# VM3300_V0_1.net
KiCad netlist of a schematic drawn in Altium Designer
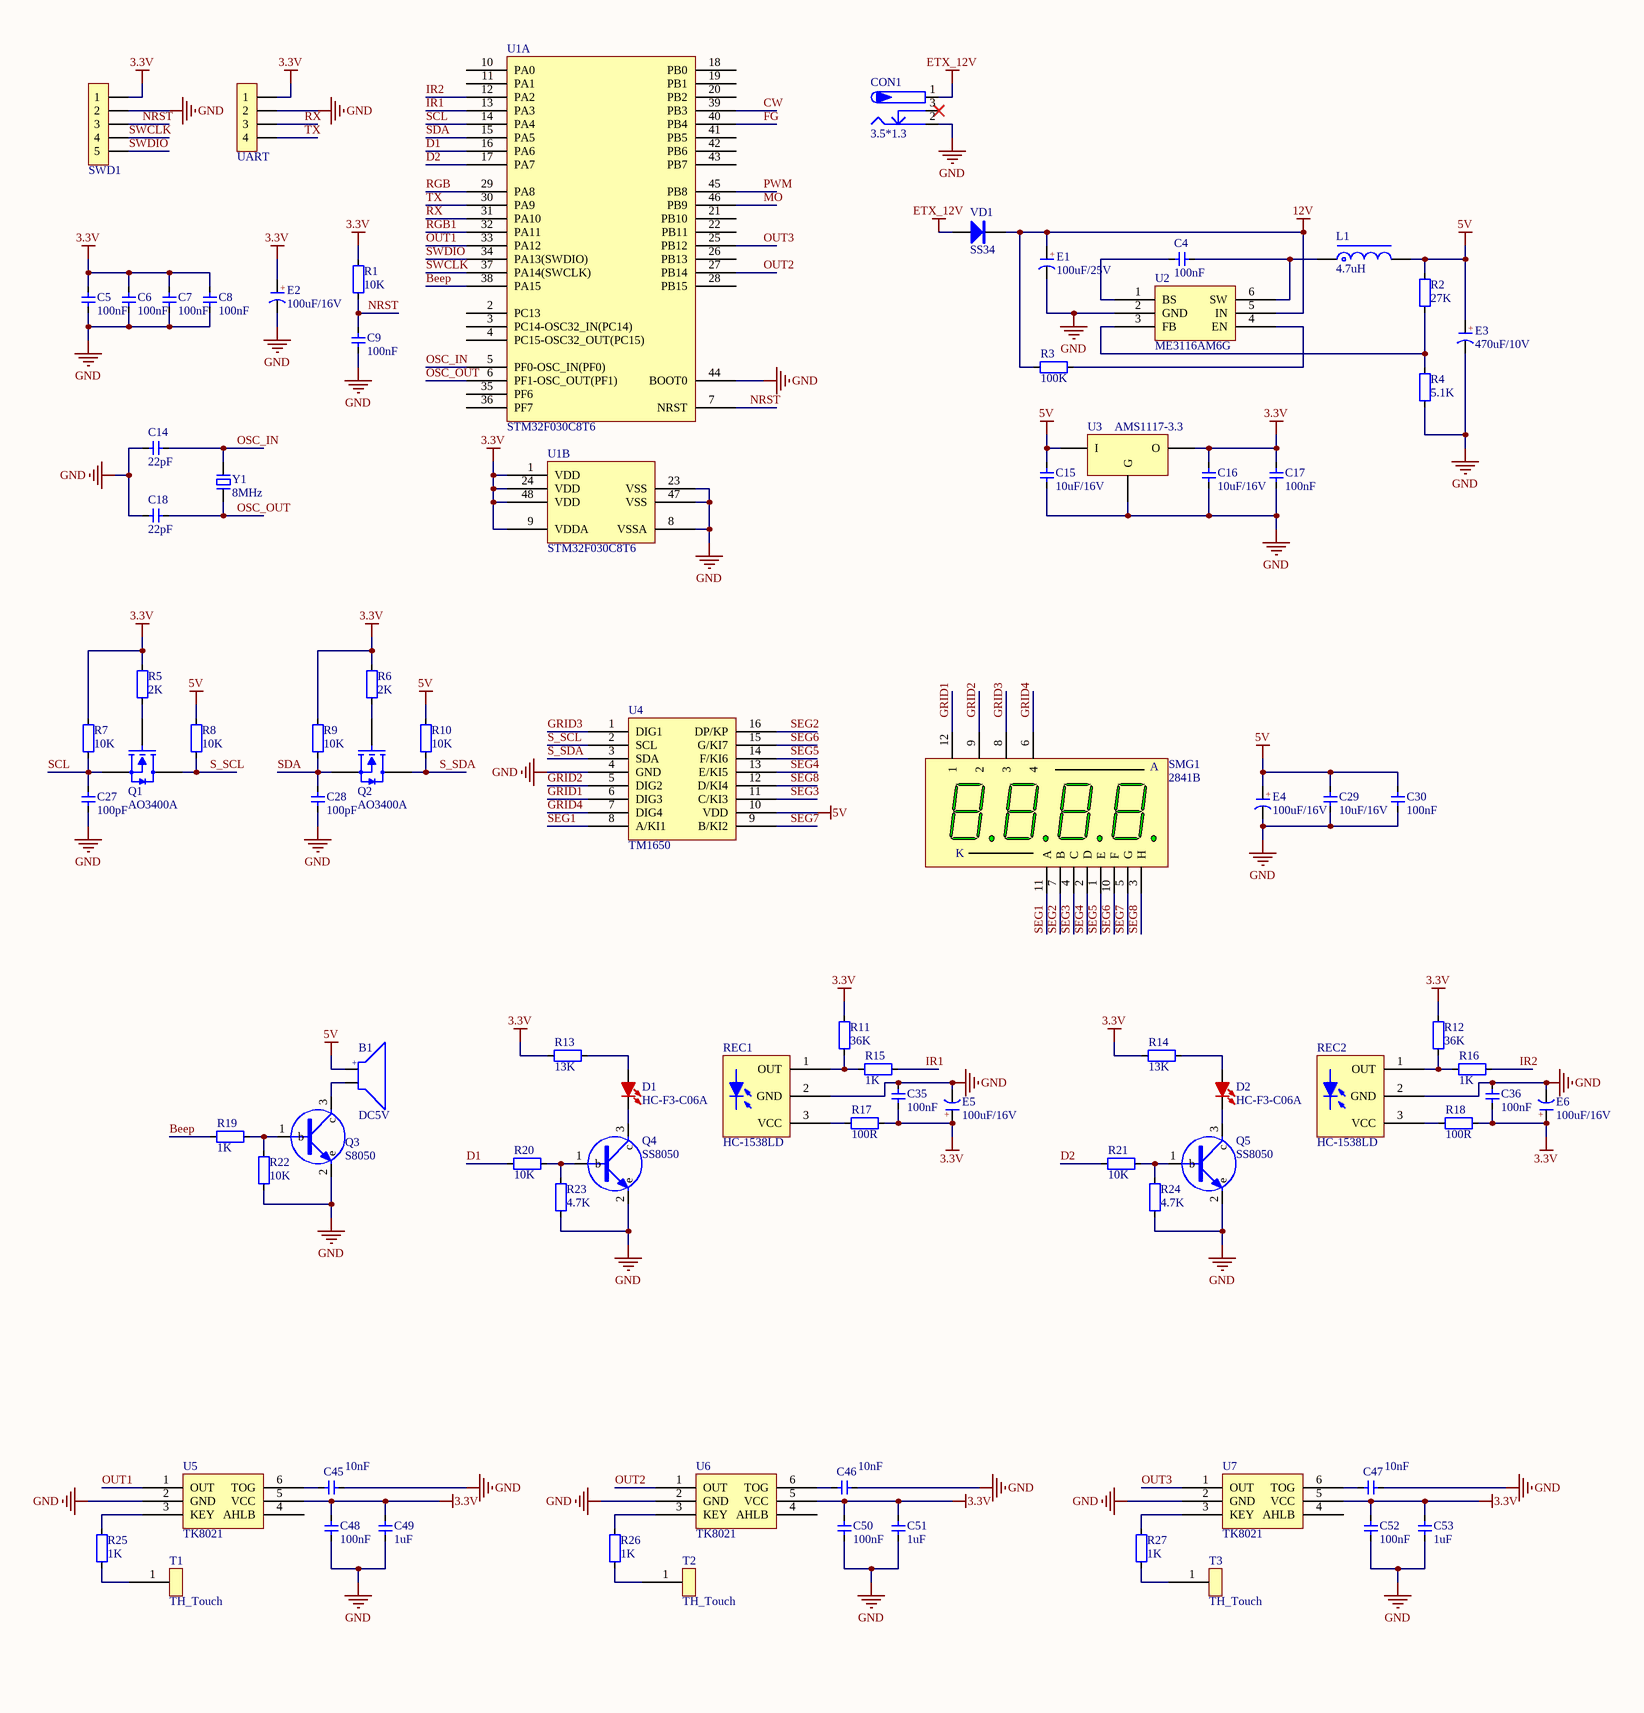
[diagram p0: VM3300_V0.1.SchDoc, left]
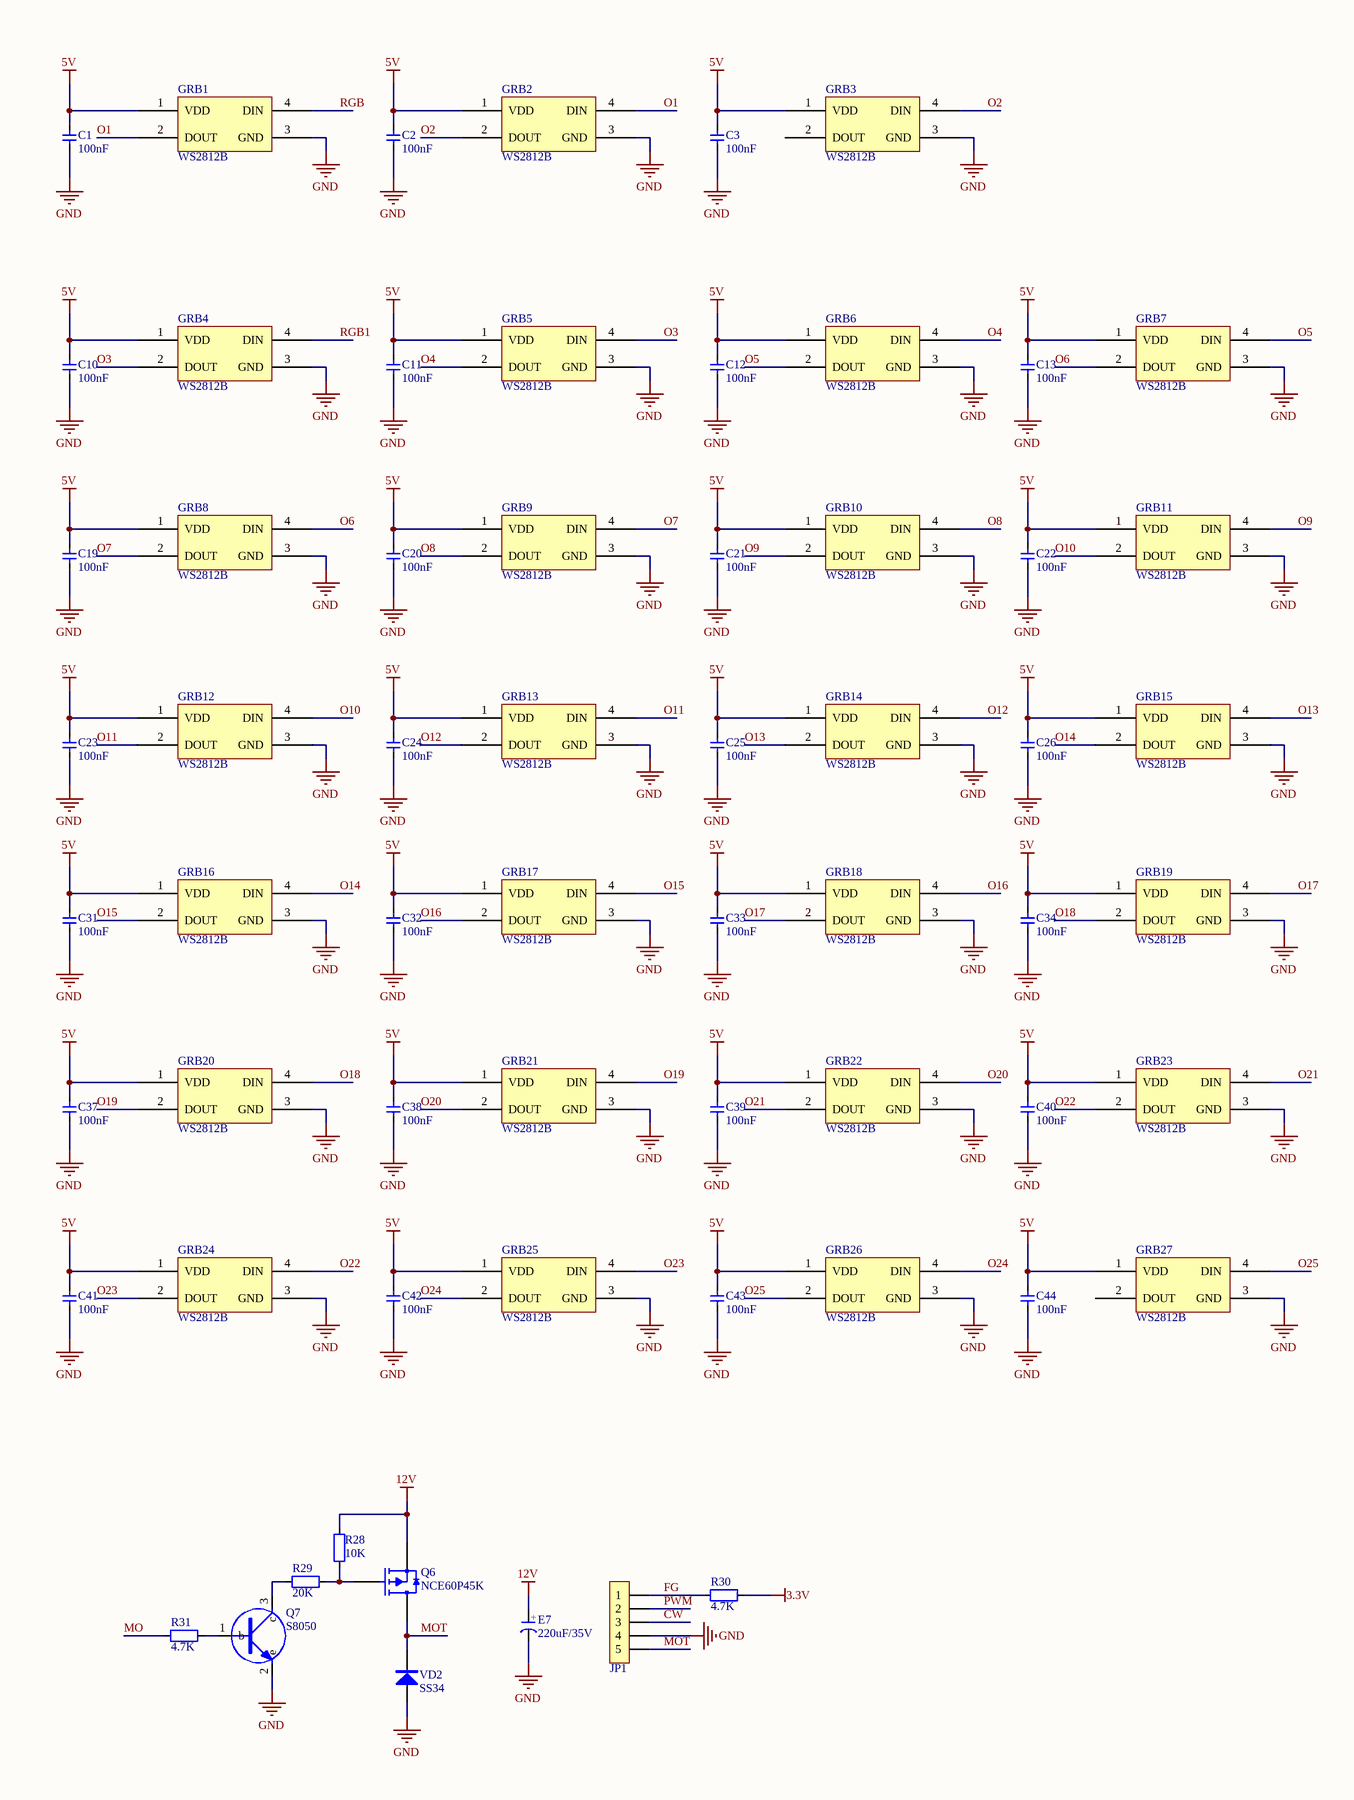
[diagram p1: VM3300_V0.1.SchDoc, right]

(export (version "E")
  (design (tool "Eeschema 10.0.6"))
  (components
    (comp (ref "B1")
      (value "DC5V")
      (footprint "BEEP 7.6x12x7.5")
      (description "蜂鸣器")
      (fields (field (name "版权归属") "源创客"))
      (libsource (lib "模块器件") (part "BEEP"))
    )
    (comp (ref "C1")
      (value "100nF")
      (footprint "C 0603")
      (description "无极性贴片电容")
      (fields (field (name "版权归属") "源创客"))
      (libsource (lib "电容") (part "C"))
    )
    (comp (ref "C2")
      (value "100nF")
      (footprint "C 0603")
      (description "无极性贴片电容")
      (fields (field (name "版权归属") "源创客"))
      (libsource (lib "电容") (part "C"))
    )
    (comp (ref "C3")
      (value "100nF")
      (footprint "C 0603")
      (description "无极性贴片电容")
      (fields (field (name "版权归属") "源创客"))
      (libsource (lib "电容") (part "C"))
    )
    (comp (ref "C4")
      (value "100nF")
      (footprint "C 0603")
      (description "无极性贴片电容")
      (fields (field (name "版权归属") "源创客"))
      (libsource (lib "电容") (part "C"))
    )
    (comp (ref "C5")
      (value "100nF")
      (footprint "C 0603")
      (description "无极性贴片电容")
      (fields (field (name "版权归属") "源创客"))
      (libsource (lib "电容") (part "C"))
    )
    (comp (ref "C6")
      (value "100nF")
      (footprint "C 0603")
      (description "无极性贴片电容")
      (fields (field (name "版权归属") "源创客"))
      (libsource (lib "电容") (part "C"))
    )
    (comp (ref "C7")
      (value "100nF")
      (footprint "C 0603")
      (description "无极性贴片电容")
      (fields (field (name "版权归属") "源创客"))
      (libsource (lib "电容") (part "C"))
    )
    (comp (ref "C8")
      (value "100nF")
      (footprint "C 0603")
      (description "无极性贴片电容")
      (fields (field (name "版权归属") "源创客"))
      (libsource (lib "电容") (part "C"))
    )
    (comp (ref "C9")
      (value "100nF")
      (footprint "C 0603")
      (description "无极性贴片电容")
      (fields (field (name "版权归属") "源创客"))
      (libsource (lib "电容") (part "C"))
    )
    (comp (ref "C10")
      (value "100nF")
      (footprint "C 0603")
      (description "无极性贴片电容")
      (fields (field (name "版权归属") "源创客"))
      (libsource (lib "电容") (part "C"))
    )
    (comp (ref "C11")
      (value "100nF")
      (footprint "C 0603")
      (description "无极性贴片电容")
      (fields (field (name "版权归属") "源创客"))
      (libsource (lib "电容") (part "C"))
    )
    (comp (ref "C12")
      (value "100nF")
      (footprint "C 0603")
      (description "无极性贴片电容")
      (fields (field (name "版权归属") "源创客"))
      (libsource (lib "电容") (part "C"))
    )
    (comp (ref "C13")
      (value "100nF")
      (footprint "C 0603")
      (description "无极性贴片电容")
      (fields (field (name "版权归属") "源创客"))
      (libsource (lib "电容") (part "C"))
    )
    (comp (ref "C14")
      (value "22pF")
      (footprint "C 0603")
      (description "无极性贴片电容")
      (fields (field (name "版权归属") "源创客"))
      (libsource (lib "电容") (part "C"))
    )
    (comp (ref "C15")
      (value "10uF/16V")
      (footprint "C 0805")
      (description "无极性贴片电容")
      (fields (field (name "版权归属") "源创客"))
      (libsource (lib "电容") (part "C"))
    )
    (comp (ref "C16")
      (value "10uF/16V")
      (footprint "C 0805")
      (description "无极性贴片电容")
      (fields (field (name "版权归属") "源创客"))
      (libsource (lib "电容") (part "C"))
    )
    (comp (ref "C17")
      (value "100nF")
      (footprint "C 0603")
      (description "无极性贴片电容")
      (fields (field (name "版权归属") "源创客"))
      (libsource (lib "电容") (part "C"))
    )
    (comp (ref "C18")
      (value "22pF")
      (footprint "C 0603")
      (description "无极性贴片电容")
      (fields (field (name "版权归属") "源创客"))
      (libsource (lib "电容") (part "C"))
    )
    (comp (ref "C19")
      (value "100nF")
      (footprint "C 0603")
      (description "无极性贴片电容")
      (fields (field (name "版权归属") "源创客"))
      (libsource (lib "电容") (part "C"))
    )
    (comp (ref "C20")
      (value "100nF")
      (footprint "C 0603")
      (description "无极性贴片电容")
      (fields (field (name "版权归属") "源创客"))
      (libsource (lib "电容") (part "C"))
    )
    (comp (ref "C21")
      (value "100nF")
      (footprint "C 0603")
      (description "无极性贴片电容")
      (fields (field (name "版权归属") "源创客"))
      (libsource (lib "电容") (part "C"))
    )
    (comp (ref "C22")
      (value "100nF")
      (footprint "C 0603")
      (description "无极性贴片电容")
      (fields (field (name "版权归属") "源创客"))
      (libsource (lib "电容") (part "C"))
    )
    (comp (ref "C23")
      (value "100nF")
      (footprint "C 0603")
      (description "无极性贴片电容")
      (fields (field (name "版权归属") "源创客"))
      (libsource (lib "电容") (part "C"))
    )
    (comp (ref "C24")
      (value "100nF")
      (footprint "C 0603")
      (description "无极性贴片电容")
      (fields (field (name "版权归属") "源创客"))
      (libsource (lib "电容") (part "C"))
    )
    (comp (ref "C25")
      (value "100nF")
      (footprint "C 0603")
      (description "无极性贴片电容")
      (fields (field (name "版权归属") "源创客"))
      (libsource (lib "电容") (part "C"))
    )
    (comp (ref "C26")
      (value "100nF")
      (footprint "C 0603")
      (description "无极性贴片电容")
      (fields (field (name "版权归属") "源创客"))
      (libsource (lib "电容") (part "C"))
    )
    (comp (ref "C27")
      (value "100pF")
      (footprint "C 0603")
      (description "无极性贴片电容")
      (fields (field (name "版权归属") "源创客"))
      (libsource (lib "电容") (part "C"))
    )
    (comp (ref "C28")
      (value "100pF")
      (footprint "C 0603")
      (description "无极性贴片电容")
      (fields (field (name "版权归属") "源创客"))
      (libsource (lib "电容") (part "C"))
    )
    (comp (ref "C29")
      (value "10uF/16V")
      (footprint "C 0805")
      (description "无极性贴片电容")
      (fields (field (name "版权归属") "源创客"))
      (libsource (lib "电容") (part "C"))
    )
    (comp (ref "C30")
      (value "100nF")
      (footprint "C 0603")
      (description "无极性贴片电容")
      (fields (field (name "版权归属") "源创客"))
      (libsource (lib "电容") (part "C"))
    )
    (comp (ref "C31")
      (value "100nF")
      (footprint "C 0603")
      (description "无极性贴片电容")
      (fields (field (name "版权归属") "源创客"))
      (libsource (lib "电容") (part "C"))
    )
    (comp (ref "C32")
      (value "100nF")
      (footprint "C 0603")
      (description "无极性贴片电容")
      (fields (field (name "版权归属") "源创客"))
      (libsource (lib "电容") (part "C"))
    )
    (comp (ref "C33")
      (value "100nF")
      (footprint "C 0603")
      (description "无极性贴片电容")
      (fields (field (name "版权归属") "源创客"))
      (libsource (lib "电容") (part "C"))
    )
    (comp (ref "C34")
      (value "100nF")
      (footprint "C 0603")
      (description "无极性贴片电容")
      (fields (field (name "版权归属") "源创客"))
      (libsource (lib "电容") (part "C"))
    )
    (comp (ref "C35")
      (value "100nF")
      (footprint "C 0603")
      (description "无极性贴片电容")
      (fields (field (name "版权归属") "源创客"))
      (libsource (lib "电容") (part "C"))
    )
    (comp (ref "C36")
      (value "100nF")
      (footprint "C 0603")
      (description "无极性贴片电容")
      (fields (field (name "版权归属") "源创客"))
      (libsource (lib "电容") (part "C"))
    )
    (comp (ref "C37")
      (value "100nF")
      (footprint "C 0603")
      (description "无极性贴片电容")
      (fields (field (name "版权归属") "源创客"))
      (libsource (lib "电容") (part "C"))
    )
    (comp (ref "C38")
      (value "100nF")
      (footprint "C 0603")
      (description "无极性贴片电容")
      (fields (field (name "版权归属") "源创客"))
      (libsource (lib "电容") (part "C"))
    )
    (comp (ref "C39")
      (value "100nF")
      (footprint "C 0603")
      (description "无极性贴片电容")
      (fields (field (name "版权归属") "源创客"))
      (libsource (lib "电容") (part "C"))
    )
    (comp (ref "C40")
      (value "100nF")
      (footprint "C 0603")
      (description "无极性贴片电容")
      (fields (field (name "版权归属") "源创客"))
      (libsource (lib "电容") (part "C"))
    )
    (comp (ref "C41")
      (value "100nF")
      (footprint "C 0603")
      (description "无极性贴片电容")
      (fields (field (name "版权归属") "源创客"))
      (libsource (lib "电容") (part "C"))
    )
    (comp (ref "C42")
      (value "100nF")
      (footprint "C 0603")
      (description "无极性贴片电容")
      (fields (field (name "版权归属") "源创客"))
      (libsource (lib "电容") (part "C"))
    )
    (comp (ref "C43")
      (value "100nF")
      (footprint "C 0603")
      (description "无极性贴片电容")
      (fields (field (name "版权归属") "源创客"))
      (libsource (lib "电容") (part "C"))
    )
    (comp (ref "C44")
      (value "100nF")
      (footprint "C 0603")
      (description "无极性贴片电容")
      (fields (field (name "版权归属") "源创客"))
      (libsource (lib "电容") (part "C"))
    )
    (comp (ref "C45")
      (value "10nF")
      (footprint "C 0603")
      (description "无极性贴片电容")
      (fields (field (name "版权归属") "源创客"))
      (libsource (lib "电容") (part "C"))
    )
    (comp (ref "C46")
      (value "10nF")
      (footprint "C 0603")
      (description "无极性贴片电容")
      (fields (field (name "版权归属") "源创客"))
      (libsource (lib "电容") (part "C"))
    )
    (comp (ref "C47")
      (value "10nF")
      (footprint "C 0603")
      (description "无极性贴片电容")
      (fields (field (name "版权归属") "源创客"))
      (libsource (lib "电容") (part "C"))
    )
    (comp (ref "C48")
      (value "100nF")
      (footprint "C 0603")
      (description "无极性贴片电容")
      (fields (field (name "版权归属") "源创客"))
      (libsource (lib "电容") (part "C"))
    )
    (comp (ref "C49")
      (value "1uF")
      (footprint "C 0603")
      (description "无极性贴片电容")
      (fields (field (name "版权归属") "源创客"))
      (libsource (lib "电容") (part "C"))
    )
    (comp (ref "C50")
      (value "100nF")
      (footprint "C 0603")
      (description "无极性贴片电容")
      (fields (field (name "版权归属") "源创客"))
      (libsource (lib "电容") (part "C"))
    )
    (comp (ref "C51")
      (value "1uF")
      (footprint "C 0603")
      (description "无极性贴片电容")
      (fields (field (name "版权归属") "源创客"))
      (libsource (lib "电容") (part "C"))
    )
    (comp (ref "C52")
      (value "100nF")
      (footprint "C 0603")
      (description "无极性贴片电容")
      (fields (field (name "版权归属") "源创客"))
      (libsource (lib "电容") (part "C"))
    )
    (comp (ref "C53")
      (value "1uF")
      (footprint "C 0603")
      (description "无极性贴片电容")
      (fields (field (name "版权归属") "源创客"))
      (libsource (lib "电容") (part "C"))
    )
    (comp (ref "CON1")
      (value "3.5*1.3")
      (footprint "DC-005")
      (description "低压电源接口")
      (fields (field (name "版权归属") "源创客"))
      (libsource (lib "接口类") (part "P-DC"))
    )
    (comp (ref "D1")
      (value "HC-F3-C06A")
      (footprint "HC-F3-C06A")
      (description "红外发射管")
      (libsource (lib "传感器") (part "HC-F3-C06A"))
    )
    (comp (ref "D2")
      (value "HC-F3-C06A")
      (footprint "HC-F3-C06A")
      (description "红外发射管")
      (libsource (lib "传感器") (part "HC-F3-C06A"))
    )
    (comp (ref "E1")
      (value "100uF/25V")
      (footprint "CAP 2.5*6.3*11.2 - BK")
      (description "直插电解电容")
      (fields (field (name "版权归属") "源创客"))
      (libsource (lib "电容") (part "C-CAP"))
    )
    (comp (ref "E2")
      (value "100uF/16V")
      (footprint "CAP 2.0*5*11 - BK")
      (description "直插电解电容")
      (fields (field (name "版权归属") "源创客"))
      (libsource (lib "电容") (part "C-CAP"))
    )
    (comp (ref "E3")
      (value "470uF/10V")
      (footprint "CAP 2.5*6.3*11.2 - BK")
      (description "直插电解电容")
      (fields (field (name "版权归属") "源创客"))
      (libsource (lib "电容") (part "C-CAP"))
    )
    (comp (ref "E4")
      (value "100uF/16V")
      (footprint "CAP 2.0*5*11 - BK")
      (description "直插电解电容")
      (fields (field (name "版权归属") "源创客"))
      (libsource (lib "电容") (part "C-CAP"))
    )
    (comp (ref "E5")
      (value "100uF/16V")
      (footprint "CAP 2.0*5*11 - BK")
      (description "直插电解电容")
      (fields (field (name "版权归属") "源创客"))
      (libsource (lib "电容") (part "C-CAP"))
    )
    (comp (ref "E6")
      (value "100uF/16V")
      (footprint "CAP 2.0*5*11 - BK")
      (description "直插电解电容")
      (fields (field (name "版权归属") "源创客"))
      (libsource (lib "电容") (part "C-CAP"))
    )
    (comp (ref "E7")
      (value "220uF/35V")
      (footprint "CAP 5.0*10*12.5 - BK")
      (description "直插电解电容")
      (fields (field (name "版权归属") "源创客"))
      (libsource (lib "电容") (part "C-CAP"))
    )
    (comp (ref "GRB1") (value "WS2812B") (footprint "WS2812B-3528") (libsource (lib "LED") (part "WS2812B")))
    (comp (ref "GRB2") (value "WS2812B") (footprint "WS2812B-3528") (libsource (lib "LED") (part "WS2812B")))
    (comp (ref "GRB3") (value "WS2812B") (footprint "WS2812B-3528") (libsource (lib "LED") (part "WS2812B")))
    (comp (ref "GRB4") (value "WS2812B") (footprint "WS2812B-3528") (libsource (lib "LED") (part "WS2812B")))
    (comp (ref "GRB5") (value "WS2812B") (footprint "WS2812B-3528") (libsource (lib "LED") (part "WS2812B")))
    (comp (ref "GRB6") (value "WS2812B") (footprint "WS2812B-3528") (libsource (lib "LED") (part "WS2812B")))
    (comp (ref "GRB7") (value "WS2812B") (footprint "WS2812B-3528") (libsource (lib "LED") (part "WS2812B")))
    (comp (ref "GRB8") (value "WS2812B") (footprint "WS2812B-3528") (libsource (lib "LED") (part "WS2812B")))
    (comp (ref "GRB9") (value "WS2812B") (footprint "WS2812B-3528") (libsource (lib "LED") (part "WS2812B")))
    (comp (ref "GRB10") (value "WS2812B") (footprint "WS2812B-3528") (libsource (lib "LED") (part "WS2812B")))
    (comp (ref "GRB11") (value "WS2812B") (footprint "WS2812B-3528") (libsource (lib "LED") (part "WS2812B")))
    (comp (ref "GRB12") (value "WS2812B") (footprint "WS2812B-3528") (libsource (lib "LED") (part "WS2812B")))
    (comp (ref "GRB13") (value "WS2812B") (footprint "WS2812B-3528") (libsource (lib "LED") (part "WS2812B")))
    (comp (ref "GRB14") (value "WS2812B") (footprint "WS2812B-3528") (libsource (lib "LED") (part "WS2812B")))
    (comp (ref "GRB15") (value "WS2812B") (footprint "WS2812B-3528") (libsource (lib "LED") (part "WS2812B")))
    (comp (ref "GRB16") (value "WS2812B") (footprint "WS2812B-3528") (libsource (lib "LED") (part "WS2812B")))
    (comp (ref "GRB17") (value "WS2812B") (footprint "WS2812B-3528") (libsource (lib "LED") (part "WS2812B")))
    (comp (ref "GRB18") (value "WS2812B") (footprint "WS2812B-3528") (libsource (lib "LED") (part "WS2812B")))
    (comp (ref "GRB19") (value "WS2812B") (footprint "WS2812B-3528") (libsource (lib "LED") (part "WS2812B")))
    (comp (ref "GRB20") (value "WS2812B") (footprint "WS2812B-3528") (libsource (lib "LED") (part "WS2812B")))
    (comp (ref "GRB21") (value "WS2812B") (footprint "WS2812B-3528") (libsource (lib "LED") (part "WS2812B")))
    (comp (ref "GRB22") (value "WS2812B") (footprint "WS2812B-3528") (libsource (lib "LED") (part "WS2812B")))
    (comp (ref "GRB23") (value "WS2812B") (footprint "WS2812B-3528") (libsource (lib "LED") (part "WS2812B")))
    (comp (ref "GRB24") (value "WS2812B") (footprint "WS2812B-3528") (libsource (lib "LED") (part "WS2812B")))
    (comp (ref "GRB25") (value "WS2812B") (footprint "WS2812B-3528") (libsource (lib "LED") (part "WS2812B")))
    (comp (ref "GRB26") (value "WS2812B") (footprint "WS2812B-3528") (libsource (lib "LED") (part "WS2812B")))
    (comp (ref "GRB27") (value "WS2812B") (footprint "WS2812B-3528") (libsource (lib "LED") (part "WS2812B")))
    (comp (ref "JP1")
      (value "HDR-1X5")
      (footprint "XH2.54-5P")
      (description "5P接插件")
      (fields (field (name "版权归属") "源创客"))
      (libsource (lib "排针-排母") (part "Header 5"))
    )
    (comp (ref "L1")
      (value "4.7uH")
      (footprint "CD32")
      (description "贴片功率电感")
      (fields (field (name "版权归属") "源创客"))
      (libsource (lib "电感") (part "L-CD"))
    )
    (comp (ref "Q1")
      (value "AO3400A")
      (footprint "SOT23-3")
      (description "N-MOS")
      (libsource (lib "三极管") (part "AO3400A"))
    )
    (comp (ref "Q2")
      (value "AO3400A")
      (footprint "SOT23-3")
      (description "N-MOS")
      (libsource (lib "三极管") (part "AO3400A"))
    )
    (comp (ref "Q3") (value "S8050") (footprint "SOT23-3L") (libsource (lib "三极管") (part "NPN")))
    (comp (ref "Q4") (value "SS8050") (footprint "SOT23-3L") (libsource (lib "三极管") (part "NPN")))
    (comp (ref "Q5") (value "SS8050") (footprint "SOT23-3L") (libsource (lib "三极管") (part "NPN")))
    (comp (ref "Q6")
      (value "NCE60P45K")
      (footprint "NCE_MOS")
      (description "NCE系类的MOS")
      (libsource (lib "三极管") (part "NCE_MOS"))
    )
    (comp (ref "Q7") (value "S8050") (footprint "SOT23-3L") (libsource (lib "三极管") (part "NPN")))
    (comp (ref "R1")
      (value "10K")
      (footprint "R 0603")
      (description "贴片电阻")
      (fields (field (name "版权归属") "源创客"))
      (libsource (lib "") (part "R_1"))
    )
    (comp (ref "R2")
      (value "27K")
      (footprint "R 0603")
      (description "贴片电阻")
      (fields (field (name "版权归属") "源创客"))
      (libsource (lib "") (part "R_1"))
    )
    (comp (ref "R3")
      (value "100K")
      (footprint "R 0603")
      (description "贴片电阻")
      (fields (field (name "版权归属") "源创客"))
      (libsource (lib "电阻") (part "R"))
    )
    (comp (ref "R4")
      (value "5.1K")
      (footprint "R 0603")
      (description "贴片电阻")
      (fields (field (name "版权归属") "源创客"))
      (libsource (lib "") (part "R_1"))
    )
    (comp (ref "R5")
      (value "2K")
      (footprint "R 0603")
      (description "贴片电阻")
      (fields (field (name "版权归属") "源创客"))
      (libsource (lib "") (part "R_1"))
    )
    (comp (ref "R6")
      (value "2K")
      (footprint "R 0603")
      (description "贴片电阻")
      (fields (field (name "版权归属") "源创客"))
      (libsource (lib "") (part "R_1"))
    )
    (comp (ref "R7")
      (value "10K")
      (footprint "R 0603")
      (description "贴片电阻")
      (fields (field (name "版权归属") "源创客"))
      (libsource (lib "") (part "R_1"))
    )
    (comp (ref "R8")
      (value "10K")
      (footprint "R 0603")
      (description "贴片电阻")
      (fields (field (name "版权归属") "源创客"))
      (libsource (lib "") (part "R_1"))
    )
    (comp (ref "R9")
      (value "10K")
      (footprint "R 0603")
      (description "贴片电阻")
      (fields (field (name "版权归属") "源创客"))
      (libsource (lib "") (part "R_1"))
    )
    (comp (ref "R10")
      (value "10K")
      (footprint "R 0603")
      (description "贴片电阻")
      (fields (field (name "版权归属") "源创客"))
      (libsource (lib "") (part "R_1"))
    )
    (comp (ref "R11")
      (value "36K")
      (footprint "R 0603")
      (description "贴片电阻")
      (fields (field (name "版权归属") "源创客"))
      (libsource (lib "") (part "R_1"))
    )
    (comp (ref "R12")
      (value "36K")
      (footprint "R 0603")
      (description "贴片电阻")
      (fields (field (name "版权归属") "源创客"))
      (libsource (lib "") (part "R_1"))
    )
    (comp (ref "R13")
      (value "13K")
      (footprint "R 0603")
      (description "贴片电阻")
      (fields (field (name "版权归属") "源创客"))
      (libsource (lib "电阻") (part "R"))
    )
    (comp (ref "R14")
      (value "13K")
      (footprint "R 0603")
      (description "贴片电阻")
      (fields (field (name "版权归属") "源创客"))
      (libsource (lib "电阻") (part "R"))
    )
    (comp (ref "R15")
      (value "1K")
      (footprint "R 0603")
      (description "贴片电阻")
      (fields (field (name "版权归属") "源创客"))
      (libsource (lib "电阻") (part "R"))
    )
    (comp (ref "R16")
      (value "1K")
      (footprint "R 0603")
      (description "贴片电阻")
      (fields (field (name "版权归属") "源创客"))
      (libsource (lib "电阻") (part "R"))
    )
    (comp (ref "R17")
      (value "100R")
      (footprint "R 0603")
      (description "贴片电阻")
      (fields (field (name "版权归属") "源创客"))
      (libsource (lib "电阻") (part "R"))
    )
    (comp (ref "R18")
      (value "100R")
      (footprint "R 0603")
      (description "贴片电阻")
      (fields (field (name "版权归属") "源创客"))
      (libsource (lib "电阻") (part "R"))
    )
    (comp (ref "R19")
      (value "1K")
      (footprint "R 0603")
      (description "贴片电阻")
      (fields (field (name "版权归属") "源创客"))
      (libsource (lib "电阻") (part "R"))
    )
    (comp (ref "R20")
      (value "10K")
      (footprint "R 0603")
      (description "贴片电阻")
      (fields (field (name "版权归属") "源创客"))
      (libsource (lib "电阻") (part "R"))
    )
    (comp (ref "R21")
      (value "10K")
      (footprint "R 0603")
      (description "贴片电阻")
      (fields (field (name "版权归属") "源创客"))
      (libsource (lib "电阻") (part "R"))
    )
    (comp (ref "R22")
      (value "10K")
      (footprint "R 0603")
      (description "贴片电阻")
      (fields (field (name "版权归属") "源创客"))
      (libsource (lib "") (part "R_1"))
    )
    (comp (ref "R23")
      (value "4.7K")
      (footprint "R 0603")
      (description "贴片电阻")
      (fields (field (name "版权归属") "源创客"))
      (libsource (lib "") (part "R_1"))
    )
    (comp (ref "R24")
      (value "4.7K")
      (footprint "R 0603")
      (description "贴片电阻")
      (fields (field (name "版权归属") "源创客"))
      (libsource (lib "") (part "R_1"))
    )
    (comp (ref "R25")
      (value "1K")
      (footprint "R 0603")
      (description "贴片电阻")
      (fields (field (name "版权归属") "源创客"))
      (libsource (lib "") (part "R_1"))
    )
    (comp (ref "R26")
      (value "1K")
      (footprint "R 0603")
      (description "贴片电阻")
      (fields (field (name "版权归属") "源创客"))
      (libsource (lib "") (part "R_1"))
    )
    (comp (ref "R27")
      (value "1K")
      (footprint "R 0603")
      (description "贴片电阻")
      (fields (field (name "版权归属") "源创客"))
      (libsource (lib "") (part "R_1"))
    )
    (comp (ref "R28")
      (value "10K")
      (footprint "R 0603")
      (description "贴片电阻")
      (fields (field (name "版权归属") "源创客"))
      (libsource (lib "") (part "R_1"))
    )
    (comp (ref "R29")
      (value "20K")
      (footprint "R 0603")
      (description "贴片电阻")
      (fields (field (name "版权归属") "源创客"))
      (libsource (lib "电阻") (part "R"))
    )
    (comp (ref "R30")
      (value "4.7K")
      (footprint "R 0603")
      (description "贴片电阻")
      (fields (field (name "版权归属") "源创客"))
      (libsource (lib "电阻") (part "R"))
    )
    (comp (ref "R31")
      (value "4.7K")
      (footprint "R 0603")
      (description "贴片电阻")
      (fields (field (name "版权归属") "源创客"))
      (libsource (lib "电阻") (part "R"))
    )
    (comp (ref "REC1")
      (value "HC-1538LD")
      (footprint "HC-1538LD")
      (description "红外接收管")
      (libsource (lib "传感器") (part "HC-1538LD"))
    )
    (comp (ref "REC2")
      (value "HC-1538LD")
      (footprint "HC-1538LD")
      (description "红外接收管")
      (libsource (lib "传感器") (part "HC-1538LD"))
    )
    (comp (ref "SMG1")
      (value "2841B")
      (footprint "SMG 0.28-4P_B")
      (description "0.28寸4位共阳数码管")
      (fields (field (name "版权归属") "源创客"))
      (libsource (lib "显示器件") (part "2841B"))
    )
    (comp (ref "SWD1")
      (value "HDR-1X5")
      (footprint "SWD_JOANLAB")
      (description "5P接插件")
      (fields (field (name "版权归属") "源创客"))
      (libsource (lib "排针-排母") (part "Header 5"))
    )
    (comp (ref "T1")
      (value "TH_Touch")
      (footprint "TH_Touch")
      (description "触摸弹簧，用于触摸感应")
      (libsource (lib "模块器件") (part "TH_Touch"))
    )
    (comp (ref "T2")
      (value "TH_Touch")
      (footprint "TH_Touch")
      (description "触摸弹簧，用于触摸感应")
      (libsource (lib "模块器件") (part "TH_Touch"))
    )
    (comp (ref "T3")
      (value "TH_Touch")
      (footprint "TH_Touch")
      (description "触摸弹簧，用于触摸感应")
      (libsource (lib "模块器件") (part "TH_Touch"))
    )
    (comp (ref "U1")
      (value "STM32F030C8T6")
      (footprint "STM32F030C8T6")
      (libsource (lib "STM32系列单片机") (part "STM32F030C8T6"))
    )
    (comp (ref "U2")
      (value "ME3116AM6G")
      (footprint "ME3116AM6G")
      (description "DC-DC电源芯片  24-40V->5V")
      (libsource (lib "变压器") (part "ME3116AM6G"))
    )
    (comp (ref "U3")
      (value "AMS1117-3.3")
      (footprint "AMS1117-3.3")
      (description "转3.3V电压")
      (libsource (lib "变压器") (part "AMS1117-3.3"))
    )
    (comp (ref "U4")
      (value "TM1650")
      (footprint "TM1650")
      (description "TM1650是一种带键盘扫描接口的LED（发光二极管显示器）驱动控制专用IC,内部集成有MCU\r\n数字接口、数据锁存器、LED驱动、键盘扫描等电路。")
      (libsource (lib "显示芯片") (part "TM1650"))
    )
    (comp (ref "U5")
      (value "TK8021")
      (footprint "TK8021")
      (description "单通道自校正触摸感应芯片")
      (libsource (lib "常用芯片") (part "TTP2233"))
    )
    (comp (ref "U6")
      (value "TK8021")
      (footprint "TK8021")
      (description "单通道自校正触摸感应芯片")
      (libsource (lib "常用芯片") (part "TTP2233"))
    )
    (comp (ref "U7")
      (value "TK8021")
      (footprint "TK8021")
      (description "单通道自校正触摸感应芯片")
      (libsource (lib "常用芯片") (part "TTP2233"))
    )
    (comp (ref "UART")
      (value "HDR-1X4")
      (footprint "XH2.54-4P")
      (description "4P接插件")
      (fields (field (name "版权归属") "源创客"))
      (libsource (lib "排针-排母") (part "Header 4"))
    )
    (comp (ref "VD1")
      (value "SS34")
      (footprint "SMA")
      (description "肖特基二极管")
      (fields (field (name "版权归属") "源创客"))
      (libsource (lib "二极管-整流桥") (part "SS34"))
    )
    (comp (ref "VD2")
      (value "SS34")
      (footprint "SMA")
      (description "肖特基二极管")
      (fields (field (name "版权归属") "源创客"))
      (libsource (lib "二极管-整流桥") (part "SS34"))
    )
    (comp (ref "Y1")
      (value "8MHz")
      (footprint "XTAL-49S SMD")
      (description "2脚晶振")
      (fields (field (name "版权归属") "源创客"))
      (libsource (lib "晶振") (part "XTAL-2"))
    )
  )
  (nets
    (net (code "1") (name "/Beep") (class "Default")
      (node (ref "R19") (pin "1") (pinfunction "1_1") (pintype "passive"))
      (node (ref "U1") (pin "38") (pinfunction "PA15_38") (pintype "passive"))
    )
    (net (code "2") (name "/CW") (class "Default")
      (node (ref "JP1") (pin "3") (pinfunction "3_3") (pintype "passive"))
      (node (ref "U1") (pin "39") (pinfunction "PB3_39") (pintype "passive"))
    )
    (net (code "3") (name "/D1") (class "Default")
      (node (ref "R20") (pin "1") (pinfunction "1_1") (pintype "passive"))
      (node (ref "U1") (pin "16") (pinfunction "PA6_16") (pintype "passive"))
    )
    (net (code "4") (name "/D2") (class "Default")
      (node (ref "R21") (pin "1") (pinfunction "1_1") (pintype "passive"))
      (node (ref "U1") (pin "17") (pinfunction "PA7_17") (pintype "passive"))
    )
    (net (code "5") (name "/FG") (class "Default")
      (node (ref "JP1") (pin "1") (pinfunction "1_1") (pintype "passive"))
      (node (ref "R30") (pin "1") (pinfunction "1_1") (pintype "passive"))
      (node (ref "U1") (pin "40") (pinfunction "PB4_40") (pintype "passive"))
    )
    (net (code "6") (name "/GRID1") (class "Default")
      (node (ref "SMG1") (pin "12") (pinfunction "1_12") (pintype "passive"))
      (node (ref "U4") (pin "6") (pinfunction "DIG3_6") (pintype "passive"))
    )
    (net (code "7") (name "/GRID2") (class "Default")
      (node (ref "SMG1") (pin "9") (pinfunction "2_9") (pintype "passive"))
      (node (ref "U4") (pin "5") (pinfunction "DIG2_5") (pintype "passive"))
    )
    (net (code "8") (name "/GRID3") (class "Default")
      (node (ref "SMG1") (pin "8") (pinfunction "3_8") (pintype "passive"))
      (node (ref "U4") (pin "1") (pinfunction "DIG1_1") (pintype "passive"))
    )
    (net (code "9") (name "/GRID4") (class "Default")
      (node (ref "SMG1") (pin "6") (pinfunction "4_6") (pintype "passive"))
      (node (ref "U4") (pin "7") (pinfunction "DIG4_7") (pintype "passive"))
    )
    (net (code "10") (name "/IR1") (class "Default")
      (node (ref "R15") (pin "2") (pinfunction "2_2") (pintype "passive"))
      (node (ref "U1") (pin "13") (pinfunction "PA3_13") (pintype "passive"))
    )
    (net (code "11") (name "/IR2") (class "Default")
      (node (ref "R16") (pin "2") (pinfunction "2_2") (pintype "passive"))
      (node (ref "U1") (pin "12") (pinfunction "PA2_12") (pintype "passive"))
    )
    (net (code "12") (name "/MO") (class "Default")
      (node (ref "R31") (pin "1") (pinfunction "1_1") (pintype "passive"))
      (node (ref "U1") (pin "46") (pinfunction "PB9_46") (pintype "passive"))
    )
    (net (code "13") (name "/MOT") (class "Default")
      (node (ref "JP1") (pin "5") (pinfunction "5_5") (pintype "passive"))
      (node (ref "Q6") (pin "2") (pinfunction "D_2") (pintype "passive"))
      (node (ref "VD2") (pin "2") (pinfunction "K_2") (pintype "passive"))
    )
    (net (code "14") (name "/NRST") (class "Default")
      (node (ref "C9") (pin "2") (pinfunction "2_2") (pintype "passive"))
      (node (ref "R1") (pin "1") (pinfunction "1_1") (pintype "passive"))
      (node (ref "SWD1") (pin "3") (pinfunction "3_3") (pintype "passive"))
      (node (ref "U1") (pin "7") (pinfunction "NRST_7") (pintype "passive"))
    )
    (net (code "15") (name "/O1") (class "Default")
      (node (ref "GRB1") (pin "2") (pinfunction "DOUT_2") (pintype "passive"))
      (node (ref "GRB2") (pin "4") (pinfunction "DIN_4") (pintype "passive"))
    )
    (net (code "16") (name "/O2") (class "Default")
      (node (ref "GRB2") (pin "2") (pinfunction "DOUT_2") (pintype "passive"))
      (node (ref "GRB3") (pin "4") (pinfunction "DIN_4") (pintype "passive"))
    )
    (net (code "17") (name "/O3") (class "Default")
      (node (ref "GRB4") (pin "2") (pinfunction "DOUT_2") (pintype "passive"))
      (node (ref "GRB5") (pin "4") (pinfunction "DIN_4") (pintype "passive"))
    )
    (net (code "18") (name "/O4") (class "Default")
      (node (ref "GRB5") (pin "2") (pinfunction "DOUT_2") (pintype "passive"))
      (node (ref "GRB6") (pin "4") (pinfunction "DIN_4") (pintype "passive"))
    )
    (net (code "19") (name "/O5") (class "Default")
      (node (ref "GRB6") (pin "2") (pinfunction "DOUT_2") (pintype "passive"))
      (node (ref "GRB7") (pin "4") (pinfunction "DIN_4") (pintype "passive"))
    )
    (net (code "20") (name "/O6") (class "Default")
      (node (ref "GRB7") (pin "2") (pinfunction "DOUT_2") (pintype "passive"))
      (node (ref "GRB8") (pin "4") (pinfunction "DIN_4") (pintype "passive"))
    )
    (net (code "21") (name "/O7") (class "Default")
      (node (ref "GRB8") (pin "2") (pinfunction "DOUT_2") (pintype "passive"))
      (node (ref "GRB9") (pin "4") (pinfunction "DIN_4") (pintype "passive"))
    )
    (net (code "22") (name "/O8") (class "Default")
      (node (ref "GRB10") (pin "4") (pinfunction "DIN_4") (pintype "passive"))
      (node (ref "GRB9") (pin "2") (pinfunction "DOUT_2") (pintype "passive"))
    )
    (net (code "23") (name "/O9") (class "Default")
      (node (ref "GRB10") (pin "2") (pinfunction "DOUT_2") (pintype "passive"))
      (node (ref "GRB11") (pin "4") (pinfunction "DIN_4") (pintype "passive"))
    )
    (net (code "24") (name "/O10") (class "Default")
      (node (ref "GRB11") (pin "2") (pinfunction "DOUT_2") (pintype "passive"))
      (node (ref "GRB12") (pin "4") (pinfunction "DIN_4") (pintype "passive"))
    )
    (net (code "25") (name "/O11") (class "Default")
      (node (ref "GRB12") (pin "2") (pinfunction "DOUT_2") (pintype "passive"))
      (node (ref "GRB13") (pin "4") (pinfunction "DIN_4") (pintype "passive"))
    )
    (net (code "26") (name "/O12") (class "Default")
      (node (ref "GRB13") (pin "2") (pinfunction "DOUT_2") (pintype "passive"))
      (node (ref "GRB14") (pin "4") (pinfunction "DIN_4") (pintype "passive"))
    )
    (net (code "27") (name "/O13") (class "Default")
      (node (ref "GRB14") (pin "2") (pinfunction "DOUT_2") (pintype "passive"))
      (node (ref "GRB15") (pin "4") (pinfunction "DIN_4") (pintype "passive"))
    )
    (net (code "28") (name "/O14") (class "Default")
      (node (ref "GRB15") (pin "2") (pinfunction "DOUT_2") (pintype "passive"))
      (node (ref "GRB16") (pin "4") (pinfunction "DIN_4") (pintype "passive"))
    )
    (net (code "29") (name "/O15") (class "Default")
      (node (ref "GRB16") (pin "2") (pinfunction "DOUT_2") (pintype "passive"))
      (node (ref "GRB17") (pin "4") (pinfunction "DIN_4") (pintype "passive"))
    )
    (net (code "30") (name "/O16") (class "Default")
      (node (ref "GRB17") (pin "2") (pinfunction "DOUT_2") (pintype "passive"))
      (node (ref "GRB18") (pin "4") (pinfunction "DIN_4") (pintype "passive"))
    )
    (net (code "31") (name "/O17") (class "Default")
      (node (ref "GRB18") (pin "2") (pinfunction "DOUT_2") (pintype "passive"))
      (node (ref "GRB19") (pin "4") (pinfunction "DIN_4") (pintype "passive"))
    )
    (net (code "32") (name "/O18") (class "Default")
      (node (ref "GRB19") (pin "2") (pinfunction "DOUT_2") (pintype "passive"))
      (node (ref "GRB20") (pin "4") (pinfunction "DIN_4") (pintype "passive"))
    )
    (net (code "33") (name "/O19") (class "Default")
      (node (ref "GRB20") (pin "2") (pinfunction "DOUT_2") (pintype "passive"))
      (node (ref "GRB21") (pin "4") (pinfunction "DIN_4") (pintype "passive"))
    )
    (net (code "34") (name "/O20") (class "Default")
      (node (ref "GRB21") (pin "2") (pinfunction "DOUT_2") (pintype "passive"))
      (node (ref "GRB22") (pin "4") (pinfunction "DIN_4") (pintype "passive"))
    )
    (net (code "35") (name "/O21") (class "Default")
      (node (ref "GRB22") (pin "2") (pinfunction "DOUT_2") (pintype "passive"))
      (node (ref "GRB23") (pin "4") (pinfunction "DIN_4") (pintype "passive"))
    )
    (net (code "36") (name "/O22") (class "Default")
      (node (ref "GRB23") (pin "2") (pinfunction "DOUT_2") (pintype "passive"))
      (node (ref "GRB24") (pin "4") (pinfunction "DIN_4") (pintype "passive"))
    )
    (net (code "37") (name "/O23") (class "Default")
      (node (ref "GRB24") (pin "2") (pinfunction "DOUT_2") (pintype "passive"))
      (node (ref "GRB25") (pin "4") (pinfunction "DIN_4") (pintype "passive"))
    )
    (net (code "38") (name "/O24") (class "Default")
      (node (ref "GRB25") (pin "2") (pinfunction "DOUT_2") (pintype "passive"))
      (node (ref "GRB26") (pin "4") (pinfunction "DIN_4") (pintype "passive"))
    )
    (net (code "39") (name "/O25") (class "Default")
      (node (ref "GRB26") (pin "2") (pinfunction "DOUT_2") (pintype "passive"))
      (node (ref "GRB27") (pin "4") (pinfunction "DIN_4") (pintype "passive"))
    )
    (net (code "40") (name "/OSC_IN") (class "Default")
      (node (ref "C14") (pin "2") (pinfunction "2_2") (pintype "passive"))
      (node (ref "U1") (pin "5") (pinfunction "PF0-OSC_IN(PF0)_5") (pintype "passive"))
      (node (ref "Y1") (pin "2") (pinfunction "2_2") (pintype "passive"))
    )
    (net (code "41") (name "/OSC_OUT") (class "Default")
      (node (ref "C18") (pin "2") (pinfunction "2_2") (pintype "passive"))
      (node (ref "U1") (pin "6") (pinfunction "PF1-OSC_OUT(PF1)_6") (pintype "passive"))
      (node (ref "Y1") (pin "1") (pinfunction "1_1") (pintype "passive"))
    )
    (net (code "42") (name "/OUT1") (class "Default")
      (node (ref "U1") (pin "33") (pinfunction "PA12_33") (pintype "passive"))
      (node (ref "U5") (pin "1") (pinfunction "OUT_1") (pintype "passive"))
    )
    (net (code "43") (name "/OUT2") (class "Default")
      (node (ref "U1") (pin "27") (pinfunction "PB14_27") (pintype "passive"))
      (node (ref "U6") (pin "1") (pinfunction "OUT_1") (pintype "passive"))
    )
    (net (code "44") (name "/OUT3") (class "Default")
      (node (ref "U1") (pin "25") (pinfunction "PB12_25") (pintype "passive"))
      (node (ref "U7") (pin "1") (pinfunction "OUT_1") (pintype "passive"))
    )
    (net (code "45") (name "/PWM") (class "Default")
      (node (ref "JP1") (pin "2") (pinfunction "2_2") (pintype "passive"))
      (node (ref "U1") (pin "45") (pinfunction "PB8_45") (pintype "passive"))
    )
    (net (code "46") (name "/RGB") (class "Default")
      (node (ref "GRB1") (pin "4") (pinfunction "DIN_4") (pintype "passive"))
      (node (ref "U1") (pin "29") (pinfunction "PA8_29") (pintype "passive"))
    )
    (net (code "47") (name "/RGB1") (class "Default")
      (node (ref "GRB4") (pin "4") (pinfunction "DIN_4") (pintype "passive"))
      (node (ref "U1") (pin "32") (pinfunction "PA11_32") (pintype "passive"))
    )
    (net (code "48") (name "/RX") (class "Default")
      (node (ref "U1") (pin "31") (pinfunction "PA10_31") (pintype "passive"))
      (node (ref "UART") (pin "3") (pinfunction "3_3") (pintype "passive"))
    )
    (net (code "49") (name "/SCL") (class "Default")
      (node (ref "C27") (pin "2") (pinfunction "2_2") (pintype "passive"))
      (node (ref "Q1") (pin "3") (pinfunction "S_3") (pintype "passive"))
      (node (ref "R7") (pin "1") (pinfunction "1_1") (pintype "passive"))
      (node (ref "U1") (pin "14") (pinfunction "PA4_14") (pintype "passive"))
    )
    (net (code "50") (name "/SDA") (class "Default")
      (node (ref "C28") (pin "2") (pinfunction "2_2") (pintype "passive"))
      (node (ref "Q2") (pin "3") (pinfunction "S_3") (pintype "passive"))
      (node (ref "R9") (pin "1") (pinfunction "1_1") (pintype "passive"))
      (node (ref "U1") (pin "15") (pinfunction "PA5_15") (pintype "passive"))
    )
    (net (code "51") (name "/SEG1") (class "Default")
      (node (ref "SMG1") (pin "11") (pinfunction "A_11") (pintype "passive"))
      (node (ref "U4") (pin "8") (pinfunction "A/KI1_8") (pintype "passive"))
    )
    (net (code "52") (name "/SEG2") (class "Default")
      (node (ref "SMG1") (pin "7") (pinfunction "B_7") (pintype "passive"))
      (node (ref "U4") (pin "16") (pinfunction "DP/KP_16") (pintype "passive"))
    )
    (net (code "53") (name "/SEG3") (class "Default")
      (node (ref "SMG1") (pin "4") (pinfunction "C_4") (pintype "passive"))
      (node (ref "U4") (pin "11") (pinfunction "C/KI3_11") (pintype "passive"))
    )
    (net (code "54") (name "/SEG4") (class "Default")
      (node (ref "SMG1") (pin "2") (pinfunction "D_2") (pintype "passive"))
      (node (ref "U4") (pin "13") (pinfunction "E/KI5_13") (pintype "passive"))
    )
    (net (code "55") (name "/SEG5") (class "Default")
      (node (ref "SMG1") (pin "1") (pinfunction "E_1") (pintype "passive"))
      (node (ref "U4") (pin "14") (pinfunction "F/KI6_14") (pintype "passive"))
    )
    (net (code "56") (name "/SEG6") (class "Default")
      (node (ref "SMG1") (pin "10") (pinfunction "F_10") (pintype "passive"))
      (node (ref "U4") (pin "15") (pinfunction "G/KI7_15") (pintype "passive"))
    )
    (net (code "57") (name "/SEG7") (class "Default")
      (node (ref "SMG1") (pin "5") (pinfunction "G_5") (pintype "passive"))
      (node (ref "U4") (pin "9") (pinfunction "B/KI2_9") (pintype "passive"))
    )
    (net (code "58") (name "/SEG8") (class "Default")
      (node (ref "SMG1") (pin "3") (pinfunction "H_3") (pintype "passive"))
      (node (ref "U4") (pin "12") (pinfunction "D/KI4_12") (pintype "passive"))
    )
    (net (code "59") (name "/SWCLK") (class "Default")
      (node (ref "SWD1") (pin "4") (pinfunction "4_4") (pintype "passive"))
      (node (ref "U1") (pin "37") (pinfunction "PA14(SWCLK)_37") (pintype "passive"))
    )
    (net (code "60") (name "/SWDIO") (class "Default")
      (node (ref "SWD1") (pin "5") (pinfunction "5_5") (pintype "passive"))
      (node (ref "U1") (pin "34") (pinfunction "PA13(SWDIO)_34") (pintype "passive"))
    )
    (net (code "61") (name "/S_SCL") (class "Default")
      (node (ref "Q1") (pin "2") (pinfunction "D_2") (pintype "passive"))
      (node (ref "R8") (pin "1") (pinfunction "1_1") (pintype "passive"))
      (node (ref "U4") (pin "2") (pinfunction "SCL_2") (pintype "passive"))
    )
    (net (code "62") (name "/S_SDA") (class "Default")
      (node (ref "Q2") (pin "2") (pinfunction "D_2") (pintype "passive"))
      (node (ref "R10") (pin "1") (pinfunction "1_1") (pintype "passive"))
      (node (ref "U4") (pin "3") (pinfunction "SDA_3") (pintype "passive"))
    )
    (net (code "63") (name "/TX") (class "Default")
      (node (ref "U1") (pin "30") (pinfunction "PA9_30") (pintype "passive"))
      (node (ref "UART") (pin "4") (pinfunction "4_4") (pintype "passive"))
    )
    (net (code "64") (name "3.3V") (class "Default")
      (node (ref "C16") (pin "2") (pinfunction "2_2") (pintype "passive"))
      (node (ref "C17") (pin "2") (pinfunction "2_2") (pintype "passive"))
      (node (ref "C35") (pin "1") (pinfunction "1_1") (pintype "passive"))
      (node (ref "C36") (pin "1") (pinfunction "1_1") (pintype "passive"))
      (node (ref "C48") (pin "2") (pinfunction "2_2") (pintype "passive"))
      (node (ref "C49") (pin "2") (pinfunction "2_2") (pintype "passive"))
      (node (ref "C5") (pin "2") (pinfunction "2_2") (pintype "passive"))
      (node (ref "C50") (pin "2") (pinfunction "2_2") (pintype "passive"))
      (node (ref "C51") (pin "2") (pinfunction "2_2") (pintype "passive"))
      (node (ref "C52") (pin "2") (pinfunction "2_2") (pintype "passive"))
      (node (ref "C53") (pin "2") (pinfunction "2_2") (pintype "passive"))
      (node (ref "C6") (pin "2") (pinfunction "2_2") (pintype "passive"))
      (node (ref "C7") (pin "2") (pinfunction "2_2") (pintype "passive"))
      (node (ref "C8") (pin "2") (pinfunction "2_2") (pintype "passive"))
      (node (ref "E2") (pin "1") (pinfunction "A_1") (pintype "passive"))
      (node (ref "E5") (pin "1") (pinfunction "A_1") (pintype "passive"))
      (node (ref "E6") (pin "1") (pinfunction "A_1") (pintype "passive"))
      (node (ref "R1") (pin "2") (pinfunction "2_2") (pintype "passive"))
      (node (ref "R11") (pin "2") (pinfunction "2_2") (pintype "passive"))
      (node (ref "R12") (pin "2") (pinfunction "2_2") (pintype "passive"))
      (node (ref "R13") (pin "1") (pinfunction "1_1") (pintype "passive"))
      (node (ref "R14") (pin "1") (pinfunction "1_1") (pintype "passive"))
      (node (ref "R17") (pin "2") (pinfunction "2_2") (pintype "passive"))
      (node (ref "R18") (pin "2") (pinfunction "2_2") (pintype "passive"))
      (node (ref "R30") (pin "2") (pinfunction "2_2") (pintype "passive"))
      (node (ref "R5") (pin "2") (pinfunction "2_2") (pintype "passive"))
      (node (ref "R6") (pin "2") (pinfunction "2_2") (pintype "passive"))
      (node (ref "R7") (pin "2") (pinfunction "2_2") (pintype "passive"))
      (node (ref "R9") (pin "2") (pinfunction "2_2") (pintype "passive"))
      (node (ref "SWD1") (pin "1") (pinfunction "1_1") (pintype "passive"))
      (node (ref "U1") (pin "1") (pinfunction "VDD_1") (pintype "passive"))
      (node (ref "U1") (pin "24") (pinfunction "VDD_24") (pintype "passive"))
      (node (ref "U1") (pin "48") (pinfunction "VDD_48") (pintype "passive"))
      (node (ref "U1") (pin "9") (pinfunction "VDDA_9") (pintype "passive"))
      (node (ref "U3") (pin "2") (pinfunction "O_2") (pintype "passive"))
      (node (ref "U5") (pin "5") (pinfunction "VCC_5") (pintype "passive"))
      (node (ref "U6") (pin "5") (pinfunction "VCC_5") (pintype "passive"))
      (node (ref "U7") (pin "5") (pinfunction "VCC_5") (pintype "passive"))
      (node (ref "UART") (pin "1") (pinfunction "1_1") (pintype "passive"))
    )
    (net (code "65") (name "5V") (class "Default")
      (node (ref "B1") (pin "1") (pinfunction "1_1") (pintype "passive"))
      (node (ref "C1") (pin "2") (pinfunction "2_2") (pintype "passive"))
      (node (ref "C10") (pin "2") (pinfunction "2_2") (pintype "passive"))
      (node (ref "C11") (pin "2") (pinfunction "2_2") (pintype "passive"))
      (node (ref "C12") (pin "2") (pinfunction "2_2") (pintype "passive"))
      (node (ref "C13") (pin "2") (pinfunction "2_2") (pintype "passive"))
      (node (ref "C15") (pin "2") (pinfunction "2_2") (pintype "passive"))
      (node (ref "C19") (pin "2") (pinfunction "2_2") (pintype "passive"))
      (node (ref "C2") (pin "2") (pinfunction "2_2") (pintype "passive"))
      (node (ref "C20") (pin "2") (pinfunction "2_2") (pintype "passive"))
      (node (ref "C21") (pin "2") (pinfunction "2_2") (pintype "passive"))
      (node (ref "C22") (pin "2") (pinfunction "2_2") (pintype "passive"))
      (node (ref "C23") (pin "2") (pinfunction "2_2") (pintype "passive"))
      (node (ref "C24") (pin "2") (pinfunction "2_2") (pintype "passive"))
      (node (ref "C25") (pin "2") (pinfunction "2_2") (pintype "passive"))
      (node (ref "C26") (pin "2") (pinfunction "2_2") (pintype "passive"))
      (node (ref "C29") (pin "2") (pinfunction "2_2") (pintype "passive"))
      (node (ref "C3") (pin "2") (pinfunction "2_2") (pintype "passive"))
      (node (ref "C30") (pin "2") (pinfunction "2_2") (pintype "passive"))
      (node (ref "C31") (pin "2") (pinfunction "2_2") (pintype "passive"))
      (node (ref "C32") (pin "2") (pinfunction "2_2") (pintype "passive"))
      (node (ref "C33") (pin "2") (pinfunction "2_2") (pintype "passive"))
      (node (ref "C34") (pin "2") (pinfunction "2_2") (pintype "passive"))
      (node (ref "C37") (pin "2") (pinfunction "2_2") (pintype "passive"))
      (node (ref "C38") (pin "2") (pinfunction "2_2") (pintype "passive"))
      (node (ref "C39") (pin "2") (pinfunction "2_2") (pintype "passive"))
      (node (ref "C40") (pin "2") (pinfunction "2_2") (pintype "passive"))
      (node (ref "C41") (pin "2") (pinfunction "2_2") (pintype "passive"))
      (node (ref "C42") (pin "2") (pinfunction "2_2") (pintype "passive"))
      (node (ref "C43") (pin "2") (pinfunction "2_2") (pintype "passive"))
      (node (ref "C44") (pin "2") (pinfunction "2_2") (pintype "passive"))
      (node (ref "E3") (pin "1") (pinfunction "A_1") (pintype "passive"))
      (node (ref "E4") (pin "1") (pinfunction "A_1") (pintype "passive"))
      (node (ref "GRB1") (pin "1") (pinfunction "VDD_1") (pintype "passive"))
      (node (ref "GRB10") (pin "1") (pinfunction "VDD_1") (pintype "passive"))
      (node (ref "GRB11") (pin "1") (pinfunction "VDD_1") (pintype "passive"))
      (node (ref "GRB12") (pin "1") (pinfunction "VDD_1") (pintype "passive"))
      (node (ref "GRB13") (pin "1") (pinfunction "VDD_1") (pintype "passive"))
      (node (ref "GRB14") (pin "1") (pinfunction "VDD_1") (pintype "passive"))
      (node (ref "GRB15") (pin "1") (pinfunction "VDD_1") (pintype "passive"))
      (node (ref "GRB16") (pin "1") (pinfunction "VDD_1") (pintype "passive"))
      (node (ref "GRB17") (pin "1") (pinfunction "VDD_1") (pintype "passive"))
      (node (ref "GRB18") (pin "1") (pinfunction "VDD_1") (pintype "passive"))
      (node (ref "GRB19") (pin "1") (pinfunction "VDD_1") (pintype "passive"))
      (node (ref "GRB2") (pin "1") (pinfunction "VDD_1") (pintype "passive"))
      (node (ref "GRB20") (pin "1") (pinfunction "VDD_1") (pintype "passive"))
      (node (ref "GRB21") (pin "1") (pinfunction "VDD_1") (pintype "passive"))
      (node (ref "GRB22") (pin "1") (pinfunction "VDD_1") (pintype "passive"))
      (node (ref "GRB23") (pin "1") (pinfunction "VDD_1") (pintype "passive"))
      (node (ref "GRB24") (pin "1") (pinfunction "VDD_1") (pintype "passive"))
      (node (ref "GRB25") (pin "1") (pinfunction "VDD_1") (pintype "passive"))
      (node (ref "GRB26") (pin "1") (pinfunction "VDD_1") (pintype "passive"))
      (node (ref "GRB27") (pin "1") (pinfunction "VDD_1") (pintype "passive"))
      (node (ref "GRB3") (pin "1") (pinfunction "VDD_1") (pintype "passive"))
      (node (ref "GRB4") (pin "1") (pinfunction "VDD_1") (pintype "passive"))
      (node (ref "GRB5") (pin "1") (pinfunction "VDD_1") (pintype "passive"))
      (node (ref "GRB6") (pin "1") (pinfunction "VDD_1") (pintype "passive"))
      (node (ref "GRB7") (pin "1") (pinfunction "VDD_1") (pintype "passive"))
      (node (ref "GRB8") (pin "1") (pinfunction "VDD_1") (pintype "passive"))
      (node (ref "GRB9") (pin "1") (pinfunction "VDD_1") (pintype "passive"))
      (node (ref "L1") (pin "2") (pinfunction "2_2") (pintype "passive"))
      (node (ref "R10") (pin "2") (pinfunction "2_2") (pintype "passive"))
      (node (ref "R2") (pin "2") (pinfunction "2_2") (pintype "passive"))
      (node (ref "R8") (pin "2") (pinfunction "2_2") (pintype "passive"))
      (node (ref "U3") (pin "3") (pinfunction "I_3") (pintype "passive"))
      (node (ref "U4") (pin "10") (pinfunction "VDD_10") (pintype "passive"))
    )
    (net (code "66") (name "12V") (class "Default")
      (node (ref "E1") (pin "1") (pinfunction "A_1") (pintype "passive"))
      (node (ref "E7") (pin "1") (pinfunction "A_1") (pintype "passive"))
      (node (ref "Q6") (pin "3") (pinfunction "S_3") (pintype "passive"))
      (node (ref "R28") (pin "2") (pinfunction "2_2") (pintype "passive"))
      (node (ref "R3") (pin "1") (pinfunction "1_1") (pintype "passive"))
      (node (ref "U2") (pin "5") (pinfunction "IN_5") (pintype "passive"))
      (node (ref "VD1") (pin "2") (pinfunction "K_2") (pintype "passive"))
    )
    (net (code "67") (name "ETX_12V") (class "Default")
      (node (ref "CON1") (pin "1") (pintype "power_in"))
      (node (ref "VD1") (pin "1") (pinfunction "A_1") (pintype "passive"))
    )
    (net (code "68") (name "GND") (class "Default")
      (node (ref "C1") (pin "1") (pinfunction "1_1") (pintype "passive"))
      (node (ref "C10") (pin "1") (pinfunction "1_1") (pintype "passive"))
      (node (ref "C11") (pin "1") (pinfunction "1_1") (pintype "passive"))
      (node (ref "C12") (pin "1") (pinfunction "1_1") (pintype "passive"))
      (node (ref "C13") (pin "1") (pinfunction "1_1") (pintype "passive"))
      (node (ref "C14") (pin "1") (pinfunction "1_1") (pintype "passive"))
      (node (ref "C15") (pin "1") (pinfunction "1_1") (pintype "passive"))
      (node (ref "C16") (pin "1") (pinfunction "1_1") (pintype "passive"))
      (node (ref "C17") (pin "1") (pinfunction "1_1") (pintype "passive"))
      (node (ref "C18") (pin "1") (pinfunction "1_1") (pintype "passive"))
      (node (ref "C19") (pin "1") (pinfunction "1_1") (pintype "passive"))
      (node (ref "C2") (pin "1") (pinfunction "1_1") (pintype "passive"))
      (node (ref "C20") (pin "1") (pinfunction "1_1") (pintype "passive"))
      (node (ref "C21") (pin "1") (pinfunction "1_1") (pintype "passive"))
      (node (ref "C22") (pin "1") (pinfunction "1_1") (pintype "passive"))
      (node (ref "C23") (pin "1") (pinfunction "1_1") (pintype "passive"))
      (node (ref "C24") (pin "1") (pinfunction "1_1") (pintype "passive"))
      (node (ref "C25") (pin "1") (pinfunction "1_1") (pintype "passive"))
      (node (ref "C26") (pin "1") (pinfunction "1_1") (pintype "passive"))
      (node (ref "C27") (pin "1") (pinfunction "1_1") (pintype "passive"))
      (node (ref "C28") (pin "1") (pinfunction "1_1") (pintype "passive"))
      (node (ref "C29") (pin "1") (pinfunction "1_1") (pintype "passive"))
      (node (ref "C3") (pin "1") (pinfunction "1_1") (pintype "passive"))
      (node (ref "C30") (pin "1") (pinfunction "1_1") (pintype "passive"))
      (node (ref "C31") (pin "1") (pinfunction "1_1") (pintype "passive"))
      (node (ref "C32") (pin "1") (pinfunction "1_1") (pintype "passive"))
      (node (ref "C33") (pin "1") (pinfunction "1_1") (pintype "passive"))
      (node (ref "C34") (pin "1") (pinfunction "1_1") (pintype "passive"))
      (node (ref "C35") (pin "2") (pinfunction "2_2") (pintype "passive"))
      (node (ref "C36") (pin "2") (pinfunction "2_2") (pintype "passive"))
      (node (ref "C37") (pin "1") (pinfunction "1_1") (pintype "passive"))
      (node (ref "C38") (pin "1") (pinfunction "1_1") (pintype "passive"))
      (node (ref "C39") (pin "1") (pinfunction "1_1") (pintype "passive"))
      (node (ref "C40") (pin "1") (pinfunction "1_1") (pintype "passive"))
      (node (ref "C41") (pin "1") (pinfunction "1_1") (pintype "passive"))
      (node (ref "C42") (pin "1") (pinfunction "1_1") (pintype "passive"))
      (node (ref "C43") (pin "1") (pinfunction "1_1") (pintype "passive"))
      (node (ref "C44") (pin "1") (pinfunction "1_1") (pintype "passive"))
      (node (ref "C45") (pin "2") (pinfunction "2_2") (pintype "passive"))
      (node (ref "C46") (pin "2") (pinfunction "2_2") (pintype "passive"))
      (node (ref "C47") (pin "2") (pinfunction "2_2") (pintype "passive"))
      (node (ref "C48") (pin "1") (pinfunction "1_1") (pintype "passive"))
      (node (ref "C49") (pin "1") (pinfunction "1_1") (pintype "passive"))
      (node (ref "C5") (pin "1") (pinfunction "1_1") (pintype "passive"))
      (node (ref "C50") (pin "1") (pinfunction "1_1") (pintype "passive"))
      (node (ref "C51") (pin "1") (pinfunction "1_1") (pintype "passive"))
      (node (ref "C52") (pin "1") (pinfunction "1_1") (pintype "passive"))
      (node (ref "C53") (pin "1") (pinfunction "1_1") (pintype "passive"))
      (node (ref "C6") (pin "1") (pinfunction "1_1") (pintype "passive"))
      (node (ref "C7") (pin "1") (pinfunction "1_1") (pintype "passive"))
      (node (ref "C8") (pin "1") (pinfunction "1_1") (pintype "passive"))
      (node (ref "C9") (pin "1") (pinfunction "1_1") (pintype "passive"))
      (node (ref "CON1") (pin "2") (pintype "power_in"))
      (node (ref "E1") (pin "2") (pinfunction "K_2") (pintype "passive"))
      (node (ref "E2") (pin "2") (pinfunction "K_2") (pintype "passive"))
      (node (ref "E3") (pin "2") (pinfunction "K_2") (pintype "passive"))
      (node (ref "E4") (pin "2") (pinfunction "K_2") (pintype "passive"))
      (node (ref "E5") (pin "2") (pinfunction "K_2") (pintype "passive"))
      (node (ref "E6") (pin "2") (pinfunction "K_2") (pintype "passive"))
      (node (ref "E7") (pin "2") (pinfunction "K_2") (pintype "passive"))
      (node (ref "GRB1") (pin "3") (pinfunction "GND_3") (pintype "passive"))
      (node (ref "GRB10") (pin "3") (pinfunction "GND_3") (pintype "passive"))
      (node (ref "GRB11") (pin "3") (pinfunction "GND_3") (pintype "passive"))
      (node (ref "GRB12") (pin "3") (pinfunction "GND_3") (pintype "passive"))
      (node (ref "GRB13") (pin "3") (pinfunction "GND_3") (pintype "passive"))
      (node (ref "GRB14") (pin "3") (pinfunction "GND_3") (pintype "passive"))
      (node (ref "GRB15") (pin "3") (pinfunction "GND_3") (pintype "passive"))
      (node (ref "GRB16") (pin "3") (pinfunction "GND_3") (pintype "passive"))
      (node (ref "GRB17") (pin "3") (pinfunction "GND_3") (pintype "passive"))
      (node (ref "GRB18") (pin "3") (pinfunction "GND_3") (pintype "passive"))
      (node (ref "GRB19") (pin "3") (pinfunction "GND_3") (pintype "passive"))
      (node (ref "GRB2") (pin "3") (pinfunction "GND_3") (pintype "passive"))
      (node (ref "GRB20") (pin "3") (pinfunction "GND_3") (pintype "passive"))
      (node (ref "GRB21") (pin "3") (pinfunction "GND_3") (pintype "passive"))
      (node (ref "GRB22") (pin "3") (pinfunction "GND_3") (pintype "passive"))
      (node (ref "GRB23") (pin "3") (pinfunction "GND_3") (pintype "passive"))
      (node (ref "GRB24") (pin "3") (pinfunction "GND_3") (pintype "passive"))
      (node (ref "GRB25") (pin "3") (pinfunction "GND_3") (pintype "passive"))
      (node (ref "GRB26") (pin "3") (pinfunction "GND_3") (pintype "passive"))
      (node (ref "GRB27") (pin "3") (pinfunction "GND_3") (pintype "passive"))
      (node (ref "GRB3") (pin "3") (pinfunction "GND_3") (pintype "passive"))
      (node (ref "GRB4") (pin "3") (pinfunction "GND_3") (pintype "passive"))
      (node (ref "GRB5") (pin "3") (pinfunction "GND_3") (pintype "passive"))
      (node (ref "GRB6") (pin "3") (pinfunction "GND_3") (pintype "passive"))
      (node (ref "GRB7") (pin "3") (pinfunction "GND_3") (pintype "passive"))
      (node (ref "GRB8") (pin "3") (pinfunction "GND_3") (pintype "passive"))
      (node (ref "GRB9") (pin "3") (pinfunction "GND_3") (pintype "passive"))
      (node (ref "JP1") (pin "4") (pinfunction "4_4") (pintype "passive"))
      (node (ref "Q3") (pin "2") (pinfunction "e_2") (pintype "passive"))
      (node (ref "Q4") (pin "2") (pinfunction "e_2") (pintype "passive"))
      (node (ref "Q5") (pin "2") (pinfunction "e_2") (pintype "passive"))
      (node (ref "Q7") (pin "2") (pinfunction "e_2") (pintype "passive"))
      (node (ref "R22") (pin "1") (pinfunction "1_1") (pintype "passive"))
      (node (ref "R23") (pin "1") (pinfunction "1_1") (pintype "passive"))
      (node (ref "R24") (pin "1") (pinfunction "1_1") (pintype "passive"))
      (node (ref "R4") (pin "1") (pinfunction "1_1") (pintype "passive"))
      (node (ref "REC1") (pin "2") (pinfunction "GND_2") (pintype "passive"))
      (node (ref "REC2") (pin "2") (pinfunction "GND_2") (pintype "passive"))
      (node (ref "SWD1") (pin "2") (pinfunction "2_2") (pintype "passive"))
      (node (ref "U1") (pin "23") (pinfunction "VSS_23") (pintype "passive"))
      (node (ref "U1") (pin "44") (pinfunction "BOOT0_44") (pintype "passive"))
      (node (ref "U1") (pin "47") (pinfunction "VSS_47") (pintype "passive"))
      (node (ref "U1") (pin "8") (pinfunction "VSSA_8") (pintype "passive"))
      (node (ref "U2") (pin "2") (pinfunction "GND_2") (pintype "passive"))
      (node (ref "U3") (pin "1") (pinfunction "G_1") (pintype "passive"))
      (node (ref "U4") (pin "4") (pinfunction "GND_4") (pintype "passive"))
      (node (ref "U5") (pin "2") (pinfunction "GND_2") (pintype "passive"))
      (node (ref "U6") (pin "2") (pinfunction "GND_2") (pintype "passive"))
      (node (ref "U7") (pin "2") (pinfunction "GND_2") (pintype "passive"))
      (node (ref "UART") (pin "2") (pinfunction "2_2") (pintype "passive"))
      (node (ref "VD2") (pin "1") (pinfunction "A_1") (pintype "passive"))
    )
    (net (code "69") (name "Net-(D1-A)") (class "Default")
      (node (ref "D1") (pin "1") (pinfunction "A_1") (pintype "passive"))
      (node (ref "R13") (pin "2") (pinfunction "2_2") (pintype "passive"))
    )
    (net (code "70") (name "Net-(D1-K)") (class "Default")
      (node (ref "D1") (pin "2") (pinfunction "K_2") (pintype "passive"))
      (node (ref "Q4") (pin "3") (pinfunction "c_3") (pintype "passive"))
    )
    (net (code "71") (name "Net-(D2-A)") (class "Default")
      (node (ref "D2") (pin "1") (pinfunction "A_1") (pintype "passive"))
      (node (ref "R14") (pin "2") (pinfunction "2_2") (pintype "passive"))
    )
    (net (code "72") (name "Net-(D2-K)") (class "Default")
      (node (ref "D2") (pin "2") (pinfunction "K_2") (pintype "passive"))
      (node (ref "Q5") (pin "3") (pinfunction "c_3") (pintype "passive"))
    )
    (net (code "73") (name "Net-(Q1-G)") (class "Default")
      (node (ref "Q1") (pin "1") (pinfunction "G_1") (pintype "passive"))
      (node (ref "R5") (pin "1") (pinfunction "1_1") (pintype "passive"))
    )
    (net (code "74") (name "Net-(Q2-G)") (class "Default")
      (node (ref "Q2") (pin "1") (pinfunction "G_1") (pintype "passive"))
      (node (ref "R6") (pin "1") (pinfunction "1_1") (pintype "passive"))
    )
    (net (code "75") (name "Net-(Q3-b)") (class "Default")
      (node (ref "Q3") (pin "1") (pinfunction "b_1") (pintype "passive"))
      (node (ref "R19") (pin "2") (pinfunction "2_2") (pintype "passive"))
      (node (ref "R22") (pin "2") (pinfunction "2_2") (pintype "passive"))
    )
    (net (code "76") (name "Net-(Q3-c)") (class "Default")
      (node (ref "B1") (pin "2") (pinfunction "2_2") (pintype "passive"))
      (node (ref "Q3") (pin "3") (pinfunction "c_3") (pintype "passive"))
    )
    (net (code "77") (name "Net-(Q4-b)") (class "Default")
      (node (ref "Q4") (pin "1") (pinfunction "b_1") (pintype "passive"))
      (node (ref "R20") (pin "2") (pinfunction "2_2") (pintype "passive"))
      (node (ref "R23") (pin "2") (pinfunction "2_2") (pintype "passive"))
    )
    (net (code "78") (name "Net-(Q5-b)") (class "Default")
      (node (ref "Q5") (pin "1") (pinfunction "b_1") (pintype "passive"))
      (node (ref "R21") (pin "2") (pinfunction "2_2") (pintype "passive"))
      (node (ref "R24") (pin "2") (pinfunction "2_2") (pintype "passive"))
    )
    (net (code "79") (name "Net-(Q6-G)") (class "Default")
      (node (ref "Q6") (pin "1") (pinfunction "G_1") (pintype "passive"))
      (node (ref "R28") (pin "1") (pinfunction "1_1") (pintype "passive"))
      (node (ref "R29") (pin "2") (pinfunction "2_2") (pintype "passive"))
    )
    (net (code "80") (name "Net-(Q7-b)") (class "Default")
      (node (ref "Q7") (pin "1") (pinfunction "b_1") (pintype "passive"))
      (node (ref "R31") (pin "2") (pinfunction "2_2") (pintype "passive"))
    )
    (net (code "81") (name "Net-(Q7-c)") (class "Default")
      (node (ref "Q7") (pin "3") (pinfunction "c_3") (pintype "passive"))
      (node (ref "R29") (pin "1") (pinfunction "1_1") (pintype "passive"))
    )
    (net (code "82") (name "Net-(R25-Pad1)") (class "Default")
      (node (ref "R25") (pin "1") (pinfunction "1_1") (pintype "passive"))
      (node (ref "T1") (pin "1") (pintype "passive"))
    )
    (net (code "83") (name "Net-(R26-Pad1)") (class "Default")
      (node (ref "R26") (pin "1") (pinfunction "1_1") (pintype "passive"))
      (node (ref "T2") (pin "1") (pintype "passive"))
    )
    (net (code "84") (name "Net-(R27-Pad1)") (class "Default")
      (node (ref "R27") (pin "1") (pinfunction "1_1") (pintype "passive"))
      (node (ref "T3") (pin "1") (pintype "passive"))
    )
    (net (code "85") (name "Net-(REC1-OUT)") (class "Default")
      (node (ref "R11") (pin "1") (pinfunction "1_1") (pintype "passive"))
      (node (ref "R15") (pin "1") (pinfunction "1_1") (pintype "passive"))
      (node (ref "REC1") (pin "1") (pinfunction "OUT_1") (pintype "passive"))
    )
    (net (code "86") (name "Net-(REC1-VCC)") (class "Default")
      (node (ref "R17") (pin "1") (pinfunction "1_1") (pintype "passive"))
      (node (ref "REC1") (pin "3") (pinfunction "VCC_3") (pintype "passive"))
    )
    (net (code "87") (name "Net-(REC2-OUT)") (class "Default")
      (node (ref "R12") (pin "1") (pinfunction "1_1") (pintype "passive"))
      (node (ref "R16") (pin "1") (pinfunction "1_1") (pintype "passive"))
      (node (ref "REC2") (pin "1") (pinfunction "OUT_1") (pintype "passive"))
    )
    (net (code "88") (name "Net-(REC2-VCC)") (class "Default")
      (node (ref "R18") (pin "1") (pinfunction "1_1") (pintype "passive"))
      (node (ref "REC2") (pin "3") (pinfunction "VCC_3") (pintype "passive"))
    )
    (net (code "89") (name "Net-(U2-BS)") (class "Default")
      (node (ref "C4") (pin "1") (pinfunction "1_1") (pintype "passive"))
      (node (ref "U2") (pin "1") (pinfunction "BS_1") (pintype "passive"))
    )
    (net (code "90") (name "Net-(U2-EN)") (class "Default")
      (node (ref "R3") (pin "2") (pinfunction "2_2") (pintype "passive"))
      (node (ref "U2") (pin "4") (pinfunction "EN_4") (pintype "passive"))
    )
    (net (code "91") (name "Net-(U2-FB)") (class "Default")
      (node (ref "R2") (pin "1") (pinfunction "1_1") (pintype "passive"))
      (node (ref "R4") (pin "2") (pinfunction "2_2") (pintype "passive"))
      (node (ref "U2") (pin "3") (pinfunction "FB_3") (pintype "passive"))
    )
    (net (code "92") (name "Net-(U2-SW)") (class "Default")
      (node (ref "C4") (pin "2") (pinfunction "2_2") (pintype "passive"))
      (node (ref "L1") (pin "1") (pinfunction "1_1") (pintype "passive"))
      (node (ref "U2") (pin "6") (pinfunction "SW_6") (pintype "passive"))
    )
    (net (code "93") (name "Net-(U5-KEY)") (class "Default")
      (node (ref "R25") (pin "2") (pinfunction "2_2") (pintype "passive"))
      (node (ref "U5") (pin "3") (pinfunction "KEY_3") (pintype "passive"))
    )
    (net (code "94") (name "Net-(U5-TOG)") (class "Default")
      (node (ref "C45") (pin "1") (pinfunction "1_1") (pintype "passive"))
      (node (ref "U5") (pin "6") (pinfunction "TOG_6") (pintype "passive"))
    )
    (net (code "95") (name "Net-(U6-KEY)") (class "Default")
      (node (ref "R26") (pin "2") (pinfunction "2_2") (pintype "passive"))
      (node (ref "U6") (pin "3") (pinfunction "KEY_3") (pintype "passive"))
    )
    (net (code "96") (name "Net-(U6-TOG)") (class "Default")
      (node (ref "C46") (pin "1") (pinfunction "1_1") (pintype "passive"))
      (node (ref "U6") (pin "6") (pinfunction "TOG_6") (pintype "passive"))
    )
    (net (code "97") (name "Net-(U7-KEY)") (class "Default")
      (node (ref "R27") (pin "2") (pinfunction "2_2") (pintype "passive"))
      (node (ref "U7") (pin "3") (pinfunction "KEY_3") (pintype "passive"))
    )
    (net (code "98") (name "Net-(U7-TOG)") (class "Default")
      (node (ref "C47") (pin "1") (pinfunction "1_1") (pintype "passive"))
      (node (ref "U7") (pin "6") (pinfunction "TOG_6") (pintype "passive"))
    )
    (net (code "99") (name "unconnected-(CON1-Pad3)") (class "Default")
      (node (ref "CON1") (pin "3") (pintype "power_in+no_connect"))
    )
    (net (code "100") (name "unconnected-(GRB3-DOUT-Pad2)") (class "Default")
      (node (ref "GRB3") (pin "2") (pinfunction "DOUT_2") (pintype "passive"))
    )
    (net (code "101") (name "unconnected-(GRB27-DOUT-Pad2)") (class "Default")
      (node (ref "GRB27") (pin "2") (pinfunction "DOUT_2") (pintype "passive"))
    )
    (net (code "102") (name "unconnected-(U1A-PA0-Pad10)") (class "Default")
      (node (ref "U1") (pin "10") (pinfunction "PA0_10") (pintype "passive"))
    )
    (net (code "103") (name "unconnected-(U1A-PA1-Pad11)") (class "Default")
      (node (ref "U1") (pin "11") (pinfunction "PA1_11") (pintype "passive"))
    )
    (net (code "104") (name "unconnected-(U1A-PB0-Pad18)") (class "Default")
      (node (ref "U1") (pin "18") (pinfunction "PB0_18") (pintype "passive"))
    )
    (net (code "105") (name "unconnected-(U1A-PB1-Pad19)") (class "Default")
      (node (ref "U1") (pin "19") (pinfunction "PB1_19") (pintype "passive"))
    )
    (net (code "106") (name "unconnected-(U1A-PB2-Pad20)") (class "Default")
      (node (ref "U1") (pin "20") (pinfunction "PB2_20") (pintype "passive"))
    )
    (net (code "107") (name "unconnected-(U1A-PB5-Pad41)") (class "Default")
      (node (ref "U1") (pin "41") (pinfunction "PB5_41") (pintype "passive"))
    )
    (net (code "108") (name "unconnected-(U1A-PB6-Pad42)") (class "Default")
      (node (ref "U1") (pin "42") (pinfunction "PB6_42") (pintype "passive"))
    )
    (net (code "109") (name "unconnected-(U1A-PB7-Pad43)") (class "Default")
      (node (ref "U1") (pin "43") (pinfunction "PB7_43") (pintype "passive"))
    )
    (net (code "110") (name "unconnected-(U1A-PB10-Pad21)") (class "Default")
      (node (ref "U1") (pin "21") (pinfunction "PB10_21") (pintype "passive"))
    )
    (net (code "111") (name "unconnected-(U1A-PB11-Pad22)") (class "Default")
      (node (ref "U1") (pin "22") (pinfunction "PB11_22") (pintype "passive"))
    )
    (net (code "112") (name "unconnected-(U1A-PB13-Pad26)") (class "Default")
      (node (ref "U1") (pin "26") (pinfunction "PB13_26") (pintype "passive"))
    )
    (net (code "113") (name "unconnected-(U1A-PB15-Pad28)") (class "Default")
      (node (ref "U1") (pin "28") (pinfunction "PB15_28") (pintype "passive"))
    )
    (net (code "114") (name "unconnected-(U1A-PC13-Pad2)") (class "Default")
      (node (ref "U1") (pin "2") (pinfunction "PC13_2") (pintype "passive"))
    )
    (net (code "115") (name "unconnected-(U1A-PC14-OSC32_IN(PC14)-Pad3)") (class "Default")
      (node (ref "U1") (pin "3") (pinfunction "PC14-OSC32_IN(PC14)_3") (pintype "passive"))
    )
    (net (code "116") (name "unconnected-(U1A-PC15-OSC32_OUT(PC15)-Pad4)") (class "Default")
      (node (ref "U1") (pin "4") (pinfunction "PC15-OSC32_OUT(PC15)_4") (pintype "passive"))
    )
    (net (code "117") (name "unconnected-(U1A-PF6-Pad35)") (class "Default")
      (node (ref "U1") (pin "35") (pinfunction "PF6_35") (pintype "passive"))
    )
    (net (code "118") (name "unconnected-(U1A-PF7-Pad36)") (class "Default")
      (node (ref "U1") (pin "36") (pinfunction "PF7_36") (pintype "passive"))
    )
    (net (code "119") (name "unconnected-(U5-AHLB-Pad4)") (class "Default")
      (node (ref "U5") (pin "4") (pinfunction "AHLB_4") (pintype "passive"))
    )
    (net (code "120") (name "unconnected-(U6-AHLB-Pad4)") (class "Default")
      (node (ref "U6") (pin "4") (pinfunction "AHLB_4") (pintype "passive"))
    )
    (net (code "121") (name "unconnected-(U7-AHLB-Pad4)") (class "Default")
      (node (ref "U7") (pin "4") (pinfunction "AHLB_4") (pintype "passive"))
    )
  )
)
